# Low_Noise_Supply.net
KiCad netlist of a schematic drawn in EAGLE
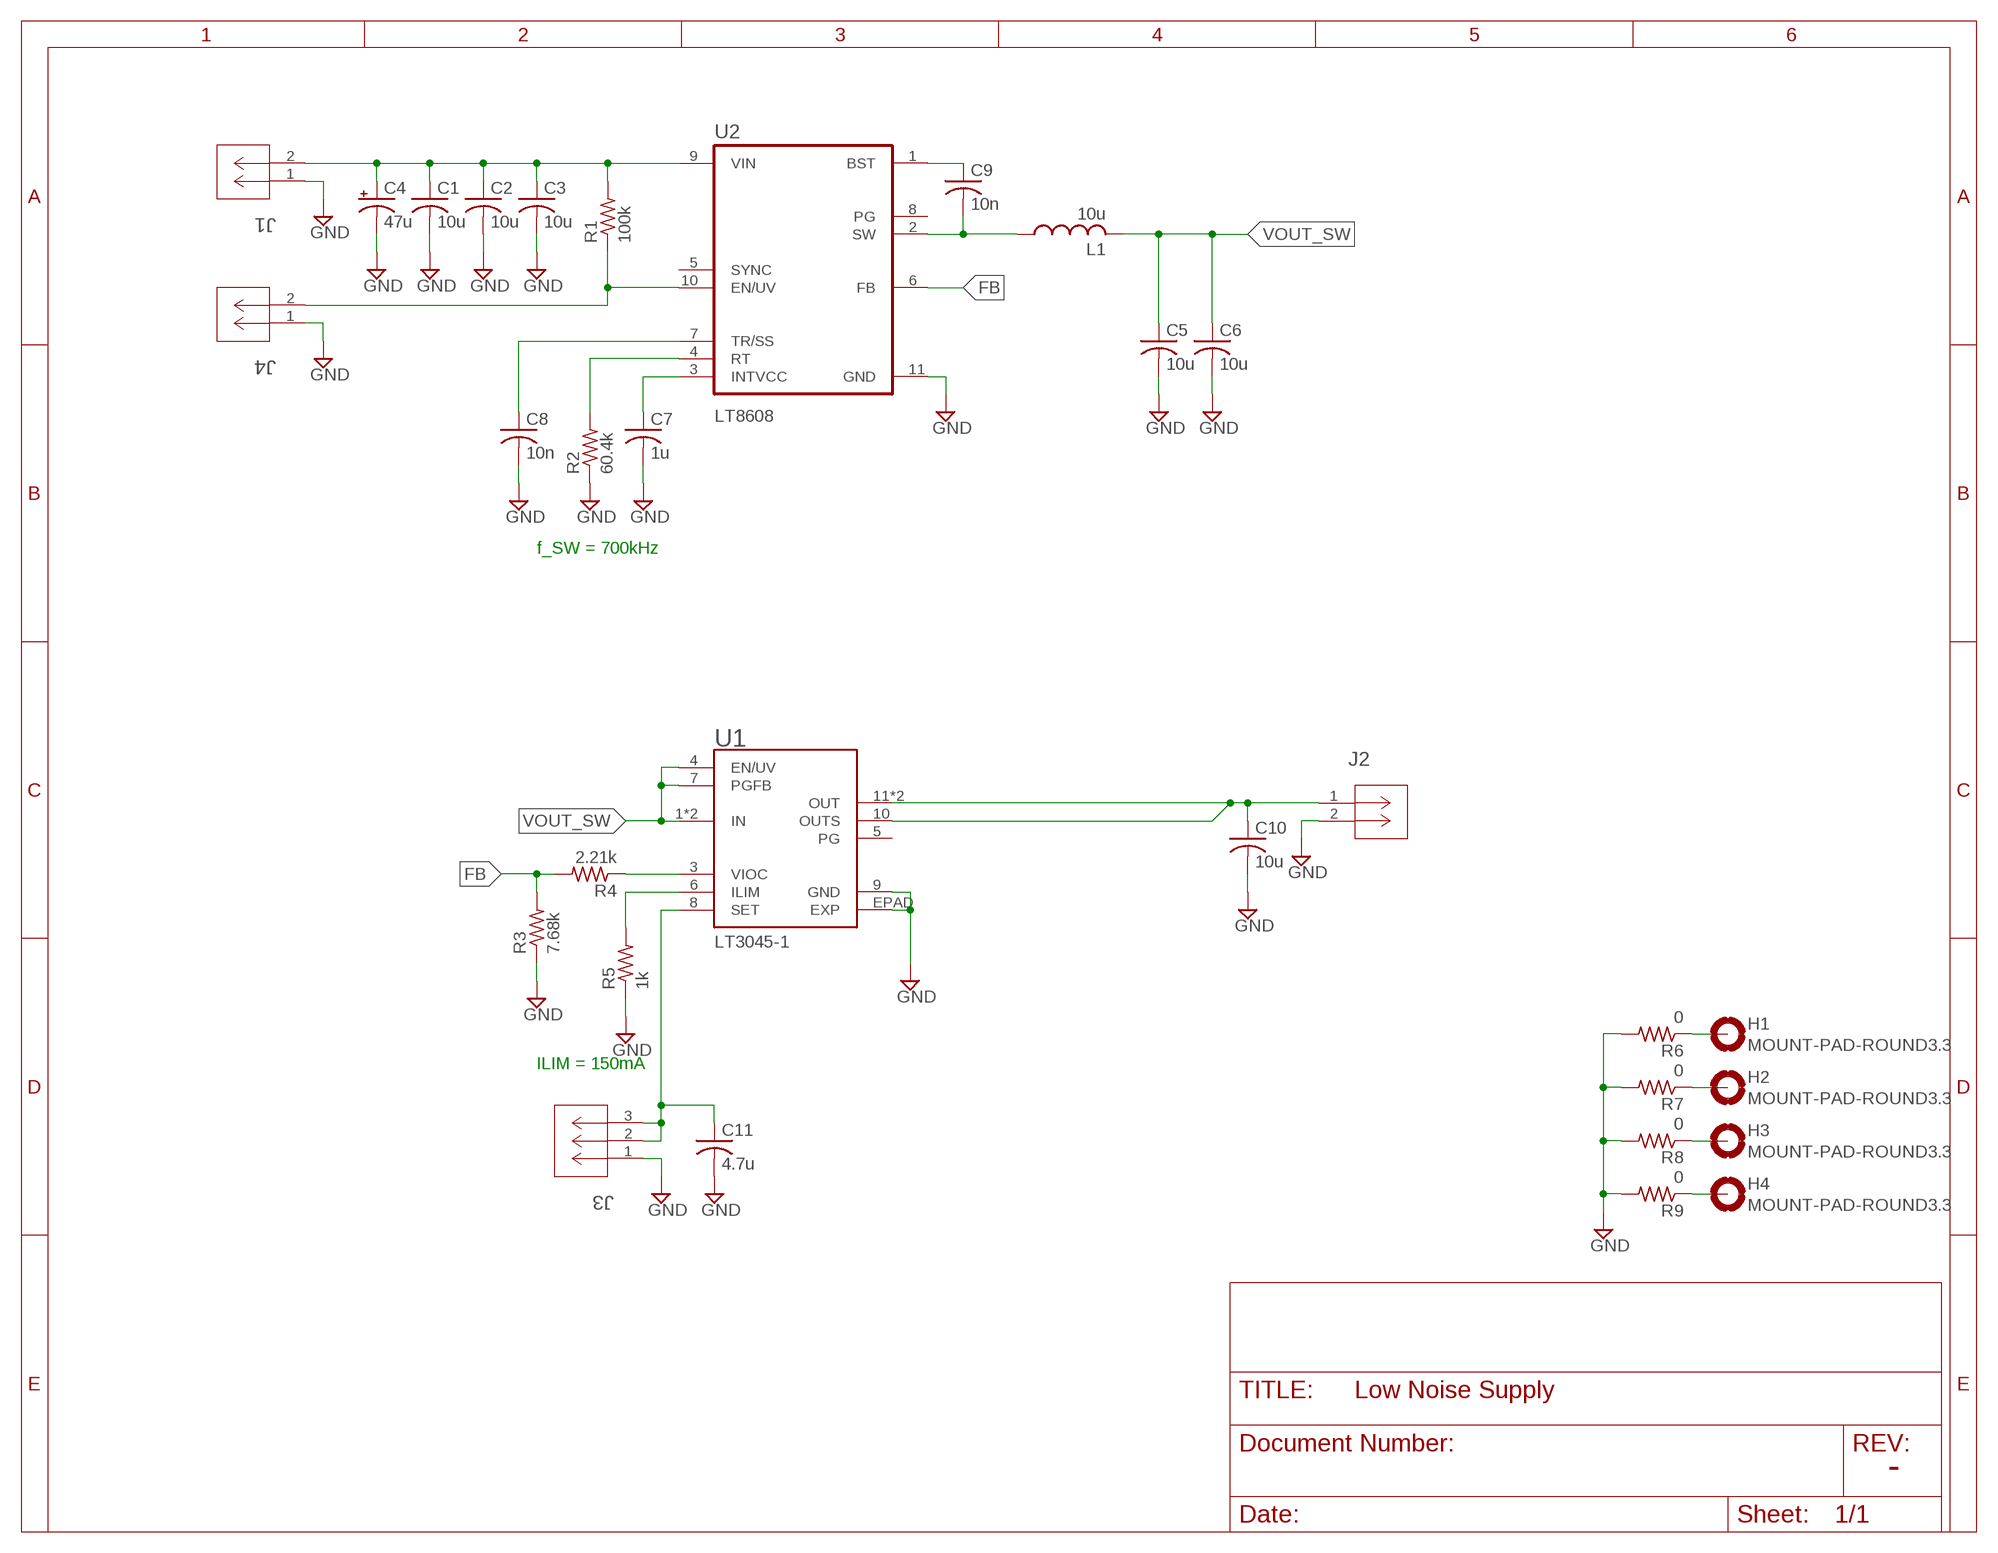
[diagram p0: schematic, sheet 1]

(export (version "E")
  (design (tool "Eeschema 10.0.6"))
  (components
    (comp (ref "C1")
      (value "10u")
      (footprint "eagle-import:C2220K")
      (libsource (lib "eagle-import") (part "C-USC2220K"))
    )
    (comp (ref "C2")
      (value "10u")
      (footprint "eagle-import:C2220K")
      (libsource (lib "eagle-import") (part "C-USC2220K"))
    )
    (comp (ref "C3")
      (value "10u")
      (footprint "eagle-import:C2220K")
      (libsource (lib "eagle-import") (part "C-USC2220K"))
    )
    (comp (ref "C4")
      (value "47u")
      (footprint "eagle-import:PANASONIC_F")
      (libsource (lib "eagle-import") (part "CPOL-USF"))
    )
    (comp (ref "C5")
      (value "10u")
      (footprint "eagle-import:C2220K")
      (libsource (lib "eagle-import") (part "C-USC2220K"))
    )
    (comp (ref "C6")
      (value "10u")
      (footprint "eagle-import:C2220K")
      (libsource (lib "eagle-import") (part "C-USC2220K"))
    )
    (comp (ref "C7")
      (value "1u")
      (footprint "eagle-import:C0805")
      (libsource (lib "eagle-import") (part "C-USC0805"))
    )
    (comp (ref "C8")
      (value "10n")
      (footprint "eagle-import:C0805")
      (libsource (lib "eagle-import") (part "C-USC0805"))
    )
    (comp (ref "C9")
      (value "10n")
      (footprint "eagle-import:C0805")
      (libsource (lib "eagle-import") (part "C-USC0805"))
    )
    (comp (ref "C10")
      (value "10u")
      (footprint "eagle-import:C2220K")
      (libsource (lib "eagle-import") (part "C-USC2220K"))
    )
    (comp (ref "C11")
      (value "4.7u")
      (footprint "eagle-import:C0805")
      (libsource (lib "eagle-import") (part "C-USC0805"))
    )
    (comp (ref "H1")
      (value "MOUNT-PAD-ROUND3.3")
      (footprint "eagle-import:3,3-PAD")
      (libsource (lib "eagle-import") (part "MOUNT-PAD-ROUND3.3"))
    )
    (comp (ref "H2")
      (value "MOUNT-PAD-ROUND3.3")
      (footprint "eagle-import:3,3-PAD")
      (libsource (lib "eagle-import") (part "MOUNT-PAD-ROUND3.3"))
    )
    (comp (ref "H3")
      (value "MOUNT-PAD-ROUND3.3")
      (footprint "eagle-import:3,3-PAD")
      (libsource (lib "eagle-import") (part "MOUNT-PAD-ROUND3.3"))
    )
    (comp (ref "H4")
      (value "MOUNT-PAD-ROUND3.3")
      (footprint "eagle-import:3,3-PAD")
      (libsource (lib "eagle-import") (part "MOUNT-PAD-ROUND3.3"))
    )
    (comp (ref "J1")
      (value "OSTVN02A150")
      (footprint "eagle-import:CONN_OSTVN02A150_OST")
      (fields (field (name "COPYRIGHT") "Copyright (C) 2022 Ultra Librarian. All rights reserved."))
      (libsource (lib "eagle-import") (part "OSTVN02A150"))
    )
    (comp (ref "J2")
      (value "OSTVN02A150")
      (footprint "eagle-import:CONN_OSTVN02A150_OST")
      (fields (field (name "COPYRIGHT") "Copyright (C) 2022 Ultra Librarian. All rights reserved."))
      (libsource (lib "eagle-import") (part "OSTVN02A150"))
    )
    (comp (ref "J3")
      (value "OSTVN03A150")
      (footprint "eagle-import:CONN3_OSTVN03A150_OST")
      (fields (field (name "COPYRIGHT") "Copyright (C) 2022 Ultra Librarian. All rights reserved."))
      (libsource (lib "eagle-import") (part "OSTVN03A150"))
    )
    (comp (ref "J4")
      (value "OSTVN02A150")
      (footprint "eagle-import:CONN_OSTVN02A150_OST")
      (fields (field (name "COPYRIGHT") "Copyright (C) 2022 Ultra Librarian. All rights reserved."))
      (libsource (lib "eagle-import") (part "OSTVN02A150"))
    )
    (comp (ref "L1")
      (value "10u")
      (footprint "eagle-import:R0805")
      (libsource (lib "eagle-import") (part "L-USL0805"))
    )
    (comp (ref "R1")
      (value "100k")
      (footprint "eagle-import:R0805")
      (libsource (lib "eagle-import") (part "R-US_R0805"))
    )
    (comp (ref "R2")
      (value "60.4k")
      (footprint "eagle-import:R0805")
      (libsource (lib "eagle-import") (part "R-US_R0805"))
    )
    (comp (ref "R3")
      (value "7.68k")
      (footprint "eagle-import:R0805")
      (libsource (lib "eagle-import") (part "R-US_R0805"))
    )
    (comp (ref "R4")
      (value "2.21k")
      (footprint "eagle-import:R0805")
      (libsource (lib "eagle-import") (part "R-US_R0805"))
    )
    (comp (ref "R5")
      (value "1k")
      (footprint "eagle-import:R0805")
      (libsource (lib "eagle-import") (part "R-US_R0805"))
    )
    (comp (ref "R6")
      (value "0")
      (footprint "eagle-import:R0805")
      (libsource (lib "eagle-import") (part "R-US_R0805"))
    )
    (comp (ref "R7")
      (value "0")
      (footprint "eagle-import:R0805")
      (libsource (lib "eagle-import") (part "R-US_R0805"))
    )
    (comp (ref "R8")
      (value "0")
      (footprint "eagle-import:R0805")
      (libsource (lib "eagle-import") (part "R-US_R0805"))
    )
    (comp (ref "R9")
      (value "0")
      (footprint "eagle-import:R0805")
      (libsource (lib "eagle-import") (part "R-US_R0805"))
    )
    (comp (ref "U1")
      (value "LT3045-1")
      (footprint "eagle-import:MSOP12_MSE_ADI-M")
      (fields
        (field (name "MANUFACTURER_PART_NUMBER") "LT3045EMSE#PBF")
        (field (name "COPYRIGHT") "Copyright (C) 2023 Ultra Librarian. All rights reserved.")
      )
      (libsource (lib "eagle-import") (part "LT3045EMSEPBFMSOP12_MSE_ADI-M"))
    )
    (comp (ref "U2")
      (value "LT8608")
      (footprint "eagle-import:MSOP-10_MSE")
      (fields (field (name "MF") "Analog Devices") (field (name "MP") "LT8608EMSE#PBF"))
      (libsource (lib "eagle-import") (part "LT8608EMSE#PBF"))
    )
  )
  (nets
    (net (code "1") (name "FB") (class "Default")
      (node (ref "R3") (pin "2") (pinfunction "2_2") (pintype "passive"))
      (node (ref "R4") (pin "2") (pinfunction "2_2") (pintype "passive"))
      (node (ref "U2") (pin "6") (pinfunction "FB_6") (pintype "input"))
    )
    (net (code "2") (name "GND") (class "Default")
      (node (ref "C1") (pin "2") (pinfunction "2_2") (pintype "passive"))
      (node (ref "C10") (pin "2") (pinfunction "2_2") (pintype "passive"))
      (node (ref "C11") (pin "2") (pinfunction "2_2") (pintype "passive"))
      (node (ref "C2") (pin "2") (pinfunction "2_2") (pintype "passive"))
      (node (ref "C3") (pin "2") (pinfunction "2_2") (pintype "passive"))
      (node (ref "C4") (pin "-") (pinfunction "-_-") (pintype "passive"))
      (node (ref "C5") (pin "2") (pinfunction "2_2") (pintype "passive"))
      (node (ref "C6") (pin "2") (pinfunction "2_2") (pintype "passive"))
      (node (ref "C7") (pin "2") (pinfunction "2_2") (pintype "passive"))
      (node (ref "C8") (pin "2") (pinfunction "2_2") (pintype "passive"))
      (node (ref "J1") (pin "1") (pinfunction "1_1") (pintype "passive"))
      (node (ref "J2") (pin "2") (pinfunction "2_2") (pintype "passive"))
      (node (ref "J3") (pin "1") (pinfunction "1_1") (pintype "passive"))
      (node (ref "J4") (pin "1") (pinfunction "1_1") (pintype "passive"))
      (node (ref "R2") (pin "1") (pinfunction "1_1") (pintype "passive"))
      (node (ref "R3") (pin "1") (pinfunction "1_1") (pintype "passive"))
      (node (ref "R5") (pin "1") (pinfunction "1_1") (pintype "passive"))
      (node (ref "R6") (pin "2") (pinfunction "2_2") (pintype "passive"))
      (node (ref "R7") (pin "2") (pinfunction "2_2") (pintype "passive"))
      (node (ref "R8") (pin "2") (pinfunction "2_2") (pintype "passive"))
      (node (ref "R9") (pin "2") (pinfunction "2_2") (pintype "passive"))
      (node (ref "U1") (pin "9") (pinfunction "GND_9") (pintype "power_in"))
      (node (ref "U1") (pin "EPAD") (pinfunction "EXP_EPAD") (pintype "power_in"))
      (node (ref "U2") (pin "11") (pinfunction "GND_11") (pintype "power_in"))
    )
    (net (code "3") (name "Net-(H1-MOUNT)") (class "Default")
      (node (ref "H1") (pin "B3,3") (pinfunction "MOUNT_B3,3") (pintype "passive"))
      (node (ref "R6") (pin "1") (pinfunction "1_1") (pintype "passive"))
    )
    (net (code "4") (name "Net-(H2-MOUNT)") (class "Default")
      (node (ref "H2") (pin "B3,3") (pinfunction "MOUNT_B3,3") (pintype "passive"))
      (node (ref "R7") (pin "1") (pinfunction "1_1") (pintype "passive"))
    )
    (net (code "5") (name "Net-(H3-MOUNT)") (class "Default")
      (node (ref "H3") (pin "B3,3") (pinfunction "MOUNT_B3,3") (pintype "passive"))
      (node (ref "R8") (pin "1") (pinfunction "1_1") (pintype "passive"))
    )
    (net (code "6") (name "Net-(H4-MOUNT)") (class "Default")
      (node (ref "H4") (pin "B3,3") (pinfunction "MOUNT_B3,3") (pintype "passive"))
      (node (ref "R9") (pin "1") (pinfunction "1_1") (pintype "passive"))
    )
    (net (code "7") (name "Net-(U1-ILIM)") (class "Default")
      (node (ref "R5") (pin "2") (pinfunction "2_2") (pintype "passive"))
      (node (ref "U1") (pin "6") (pinfunction "ILIM_6") (pintype "passive"))
    )
    (net (code "8") (name "Net-(U1-OUTS)") (class "Default")
      (node (ref "C10") (pin "1") (pinfunction "1_1") (pintype "passive"))
      (node (ref "J2") (pin "1") (pinfunction "1_1") (pintype "passive"))
      (node (ref "U1") (pin "10") (pinfunction "OUTS_10") (pintype "output"))
      (node (ref "U1") (pin "11") (pinfunction "OUT_11") (pintype "output"))
      (node (ref "U1") (pin "12") (pinfunction "OUT_12") (pintype "output"))
    )
    (net (code "9") (name "Net-(U1-SET)") (class "Default")
      (node (ref "C11") (pin "1") (pinfunction "1_1") (pintype "passive"))
      (node (ref "J3") (pin "2") (pinfunction "2_2") (pintype "passive"))
      (node (ref "J3") (pin "3") (pinfunction "3_3") (pintype "passive"))
      (node (ref "U1") (pin "8") (pinfunction "SET_8") (pintype "input"))
    )
    (net (code "10") (name "Net-(U1-VIOC)") (class "Default")
      (node (ref "R4") (pin "1") (pinfunction "1_1") (pintype "passive"))
      (node (ref "U1") (pin "3") (pinfunction "VIOC_3") (pintype "power_in"))
    )
    (net (code "11") (name "Net-(U2-BST)") (class "Default")
      (node (ref "C9") (pin "1") (pinfunction "1_1") (pintype "passive"))
      (node (ref "U2") (pin "1") (pinfunction "BST_1") (pintype "bidirectional"))
    )
    (net (code "12") (name "Net-(U2-EN{slash}UV)") (class "Default")
      (node (ref "J4") (pin "2") (pinfunction "2_2") (pintype "passive"))
      (node (ref "R1") (pin "1") (pinfunction "1_1") (pintype "passive"))
      (node (ref "U2") (pin "10") (pinfunction "EN/UV_10") (pintype "input"))
    )
    (net (code "13") (name "Net-(U2-INTVCC)") (class "Default")
      (node (ref "C7") (pin "1") (pinfunction "1_1") (pintype "passive"))
      (node (ref "U2") (pin "3") (pinfunction "INTVCC_3") (pintype "power_in"))
    )
    (net (code "14") (name "Net-(U2-RT)") (class "Default")
      (node (ref "R2") (pin "2") (pinfunction "2_2") (pintype "passive"))
      (node (ref "U2") (pin "4") (pinfunction "RT_4") (pintype "input"))
    )
    (net (code "15") (name "Net-(U2-SW)") (class "Default")
      (node (ref "C9") (pin "2") (pinfunction "2_2") (pintype "passive"))
      (node (ref "L1") (pin "1") (pinfunction "1_1") (pintype "passive"))
      (node (ref "U2") (pin "2") (pinfunction "SW_2") (pintype "output"))
    )
    (net (code "16") (name "Net-(U2-TR{slash}SS)") (class "Default")
      (node (ref "C8") (pin "1") (pinfunction "1_1") (pintype "passive"))
      (node (ref "U2") (pin "7") (pinfunction "TR/SS_7") (pintype "bidirectional"))
    )
    (net (code "17") (name "Net-(U2-VIN)") (class "Default")
      (node (ref "C1") (pin "1") (pinfunction "1_1") (pintype "passive"))
      (node (ref "C2") (pin "1") (pinfunction "1_1") (pintype "passive"))
      (node (ref "C3") (pin "1") (pinfunction "1_1") (pintype "passive"))
      (node (ref "C4") (pin "+") (pinfunction "+_+") (pintype "passive"))
      (node (ref "J1") (pin "2") (pinfunction "2_2") (pintype "passive"))
      (node (ref "R1") (pin "2") (pinfunction "2_2") (pintype "passive"))
      (node (ref "U2") (pin "9") (pinfunction "VIN_9") (pintype "power_in"))
    )
    (net (code "18") (name "VOUT_SW") (class "Default")
      (node (ref "C5") (pin "1") (pinfunction "1_1") (pintype "passive"))
      (node (ref "C6") (pin "1") (pinfunction "1_1") (pintype "passive"))
      (node (ref "L1") (pin "2") (pinfunction "2_2") (pintype "passive"))
      (node (ref "U1") (pin "1") (pinfunction "IN_1") (pintype "input"))
      (node (ref "U1") (pin "2") (pinfunction "IN_2") (pintype "input"))
      (node (ref "U1") (pin "4") (pinfunction "EN/UV_4") (pintype "input"))
      (node (ref "U1") (pin "7") (pinfunction "PGFB_7") (pintype "output"))
    )
    (net (code "19") (name "unconnected-(U1-PG-Pad5)") (class "Default")
      (node (ref "U1") (pin "5") (pinfunction "PG_5") (pintype "output"))
    )
    (net (code "20") (name "unconnected-(U2-PG-Pad8)") (class "Default")
      (node (ref "U2") (pin "8") (pinfunction "PG_8") (pintype "output"))
    )
    (net (code "21") (name "unconnected-(U2-SYNC-Pad5)") (class "Default")
      (node (ref "U2") (pin "5") (pinfunction "SYNC_5") (pintype "input"))
    )
  )
)
